# main.net
KiCad netlist of a schematic drawn in Altium Designer
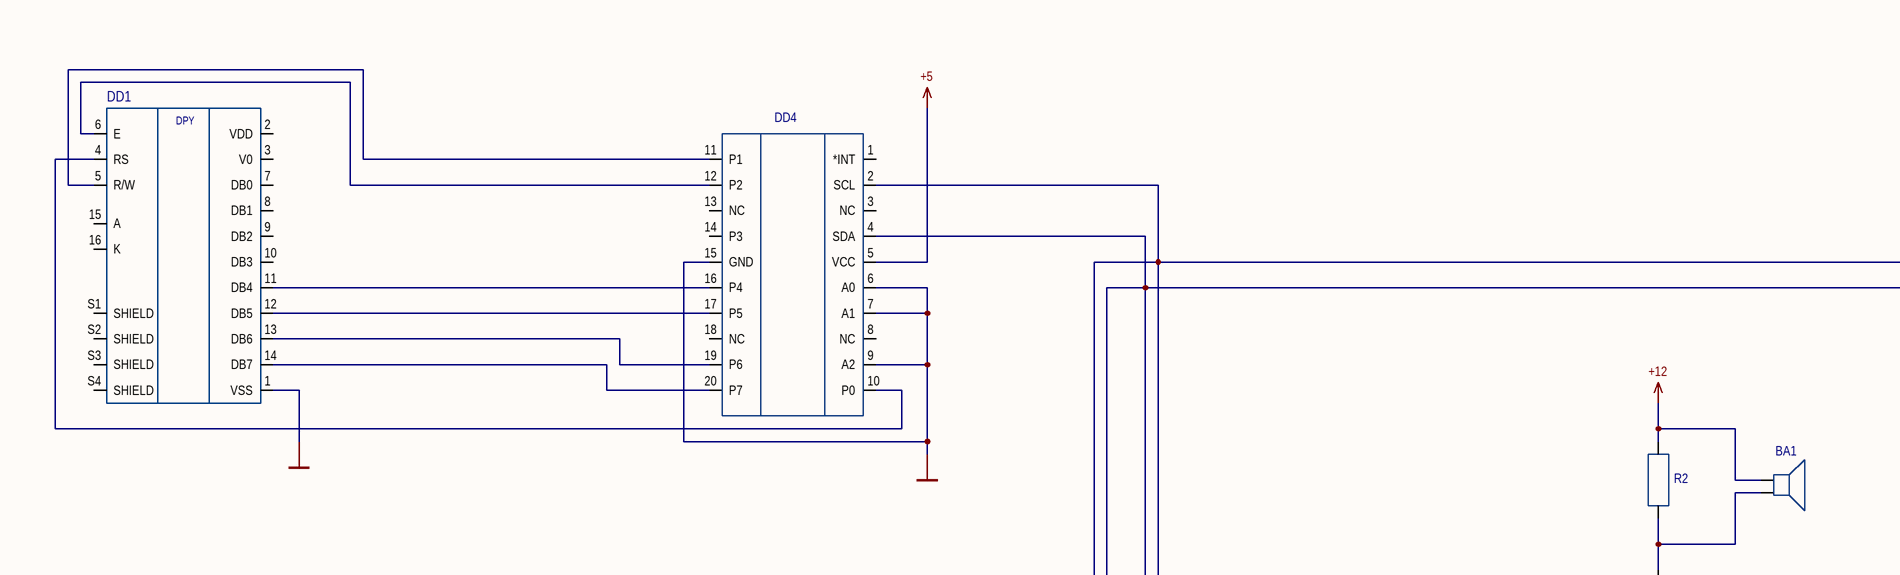
[diagram p0: main.SchDoc, top left]
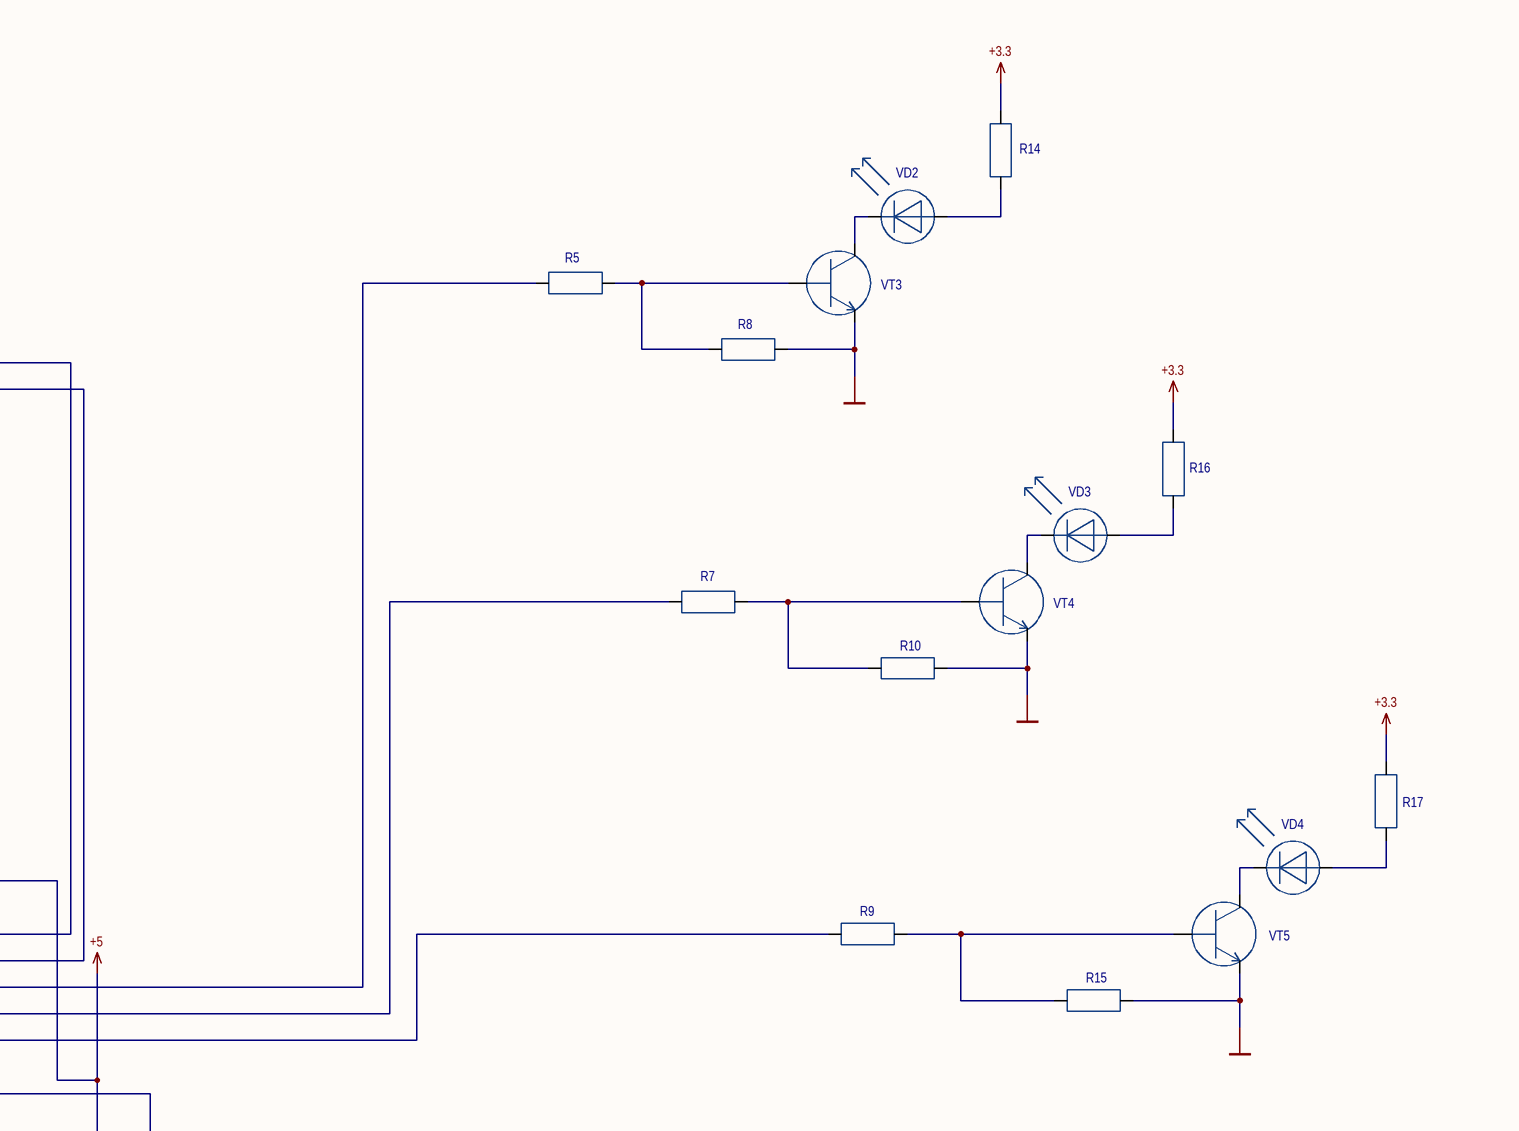
[diagram p1: main.SchDoc, top right]
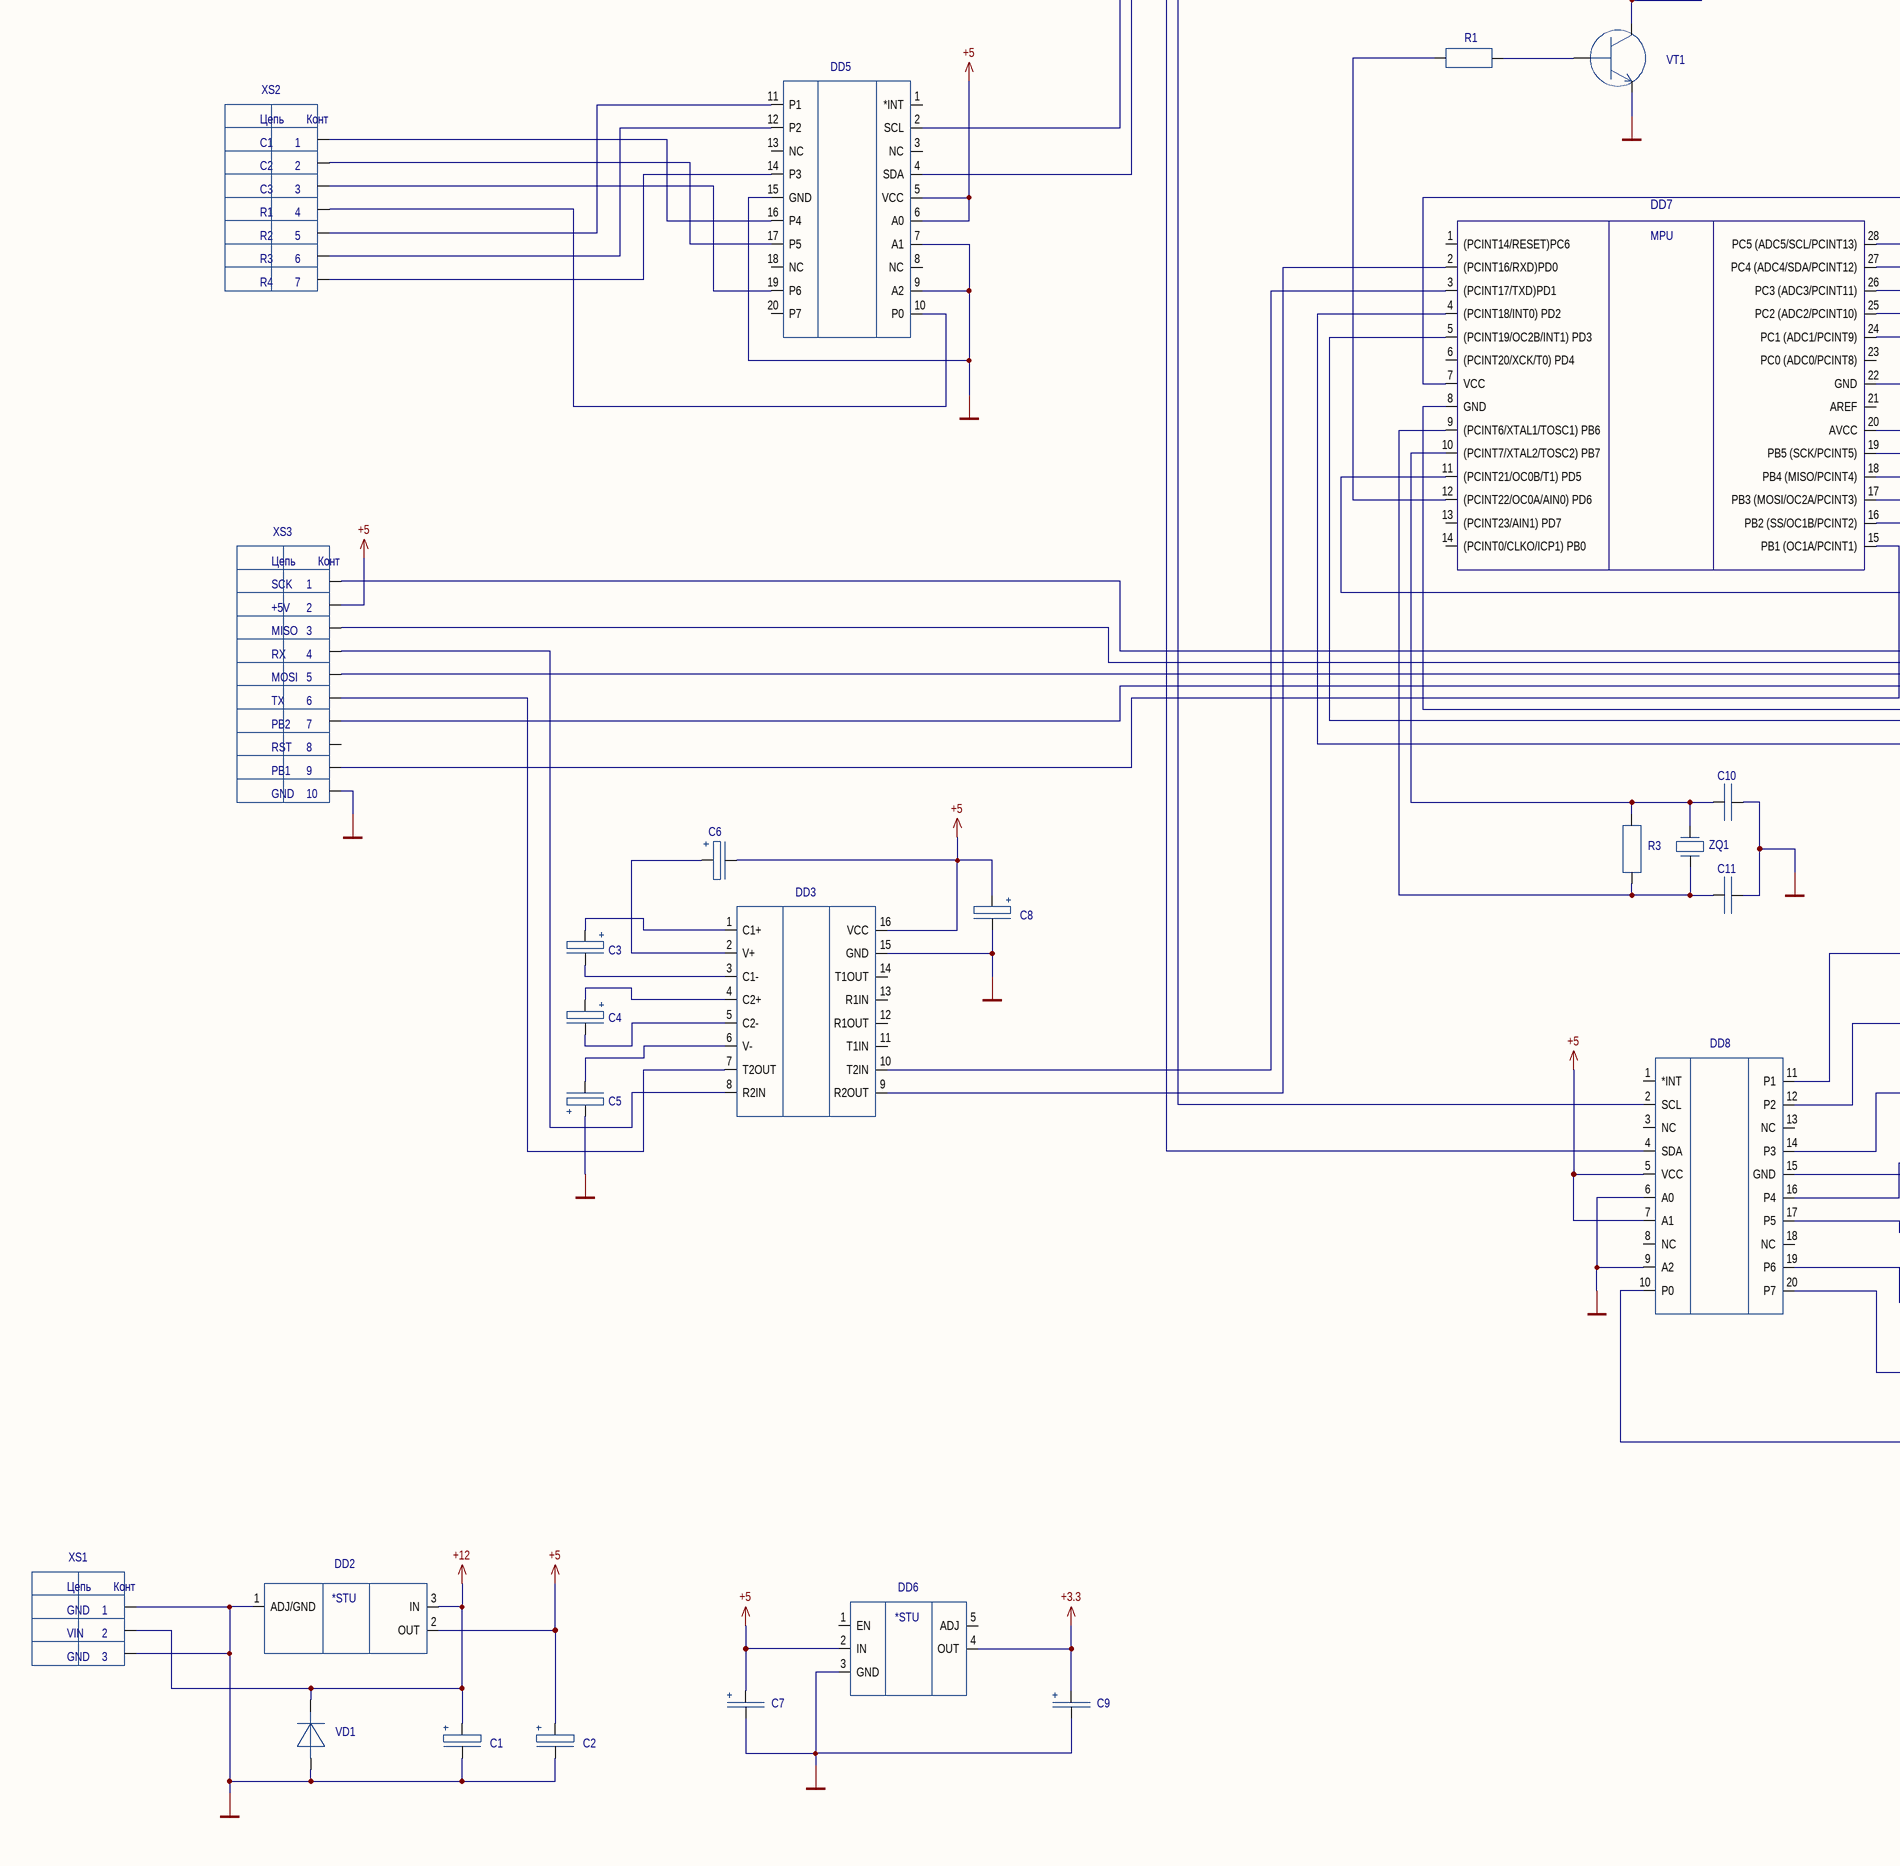
[diagram p2: main.SchDoc, bottom left]
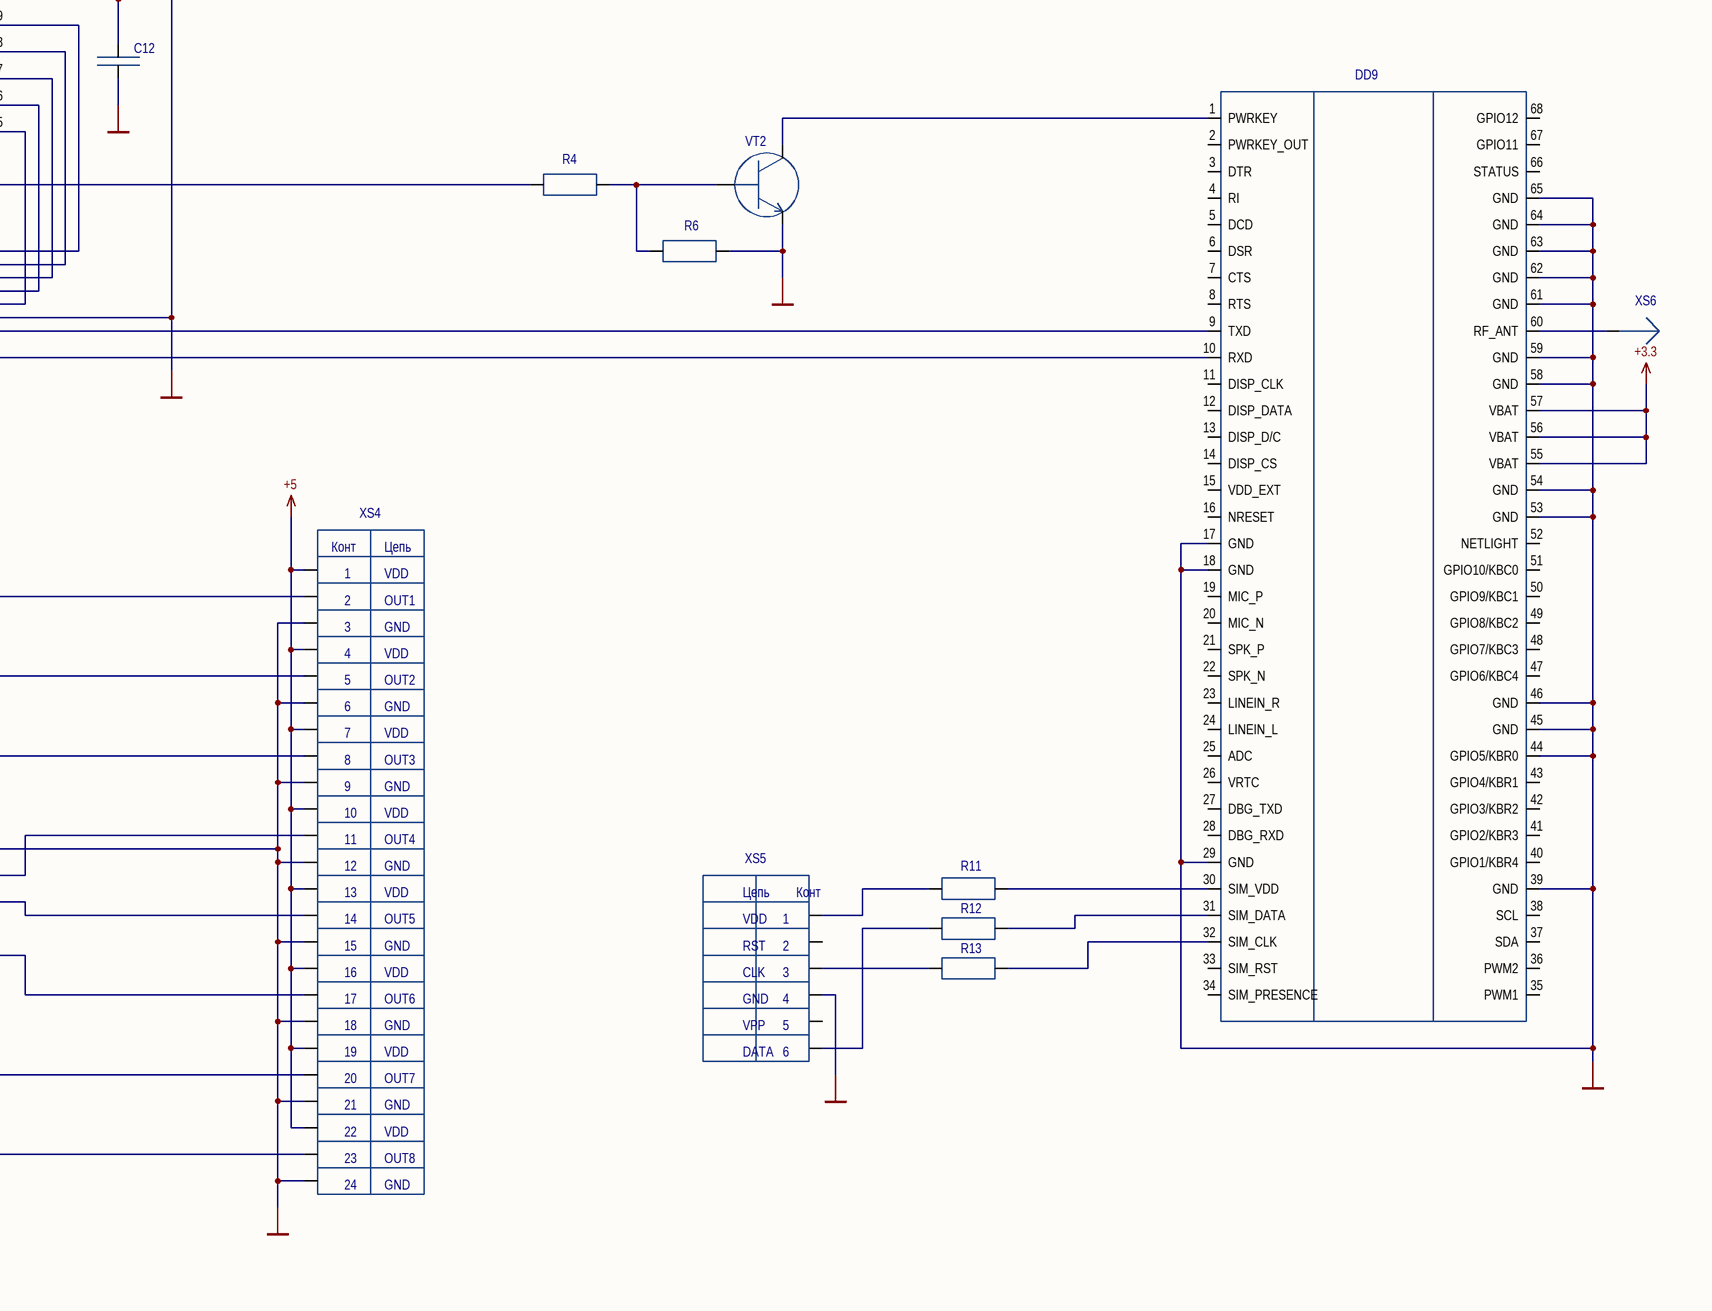
[diagram p3: main.SchDoc, bottom right]

(export (version "E")
  (design (tool "Eeschema 10.0.6"))
  (components
    (comp (ref "BA1")
      (value "speaker_CVS-1508")
      (footprint "diploma:SPeaKeR_CVS-1508")
      (libsource (lib "diploma") (part "speaker_CVS-1508"))
    )
    (comp (ref "C1")
      (value "pol_10mkF")
      (footprint "diploma:PCAP_6_3x11THRU-ELECT_NCA")
      (libsource (lib "diploma") (part "cap_pol_10mkF"))
    )
    (comp (ref "C2")
      (value "pol_10mkF")
      (footprint "diploma:PCAP_6_3x11THRU-ELECT_NCA")
      (libsource (lib "diploma") (part "cap_pol_10mkF"))
    )
    (comp (ref "C3")
      (value "pol_1mkF")
      (footprint "PCAP_5x11-THRU-ELECT_NCA")
      (libsource (lib "diploma") (part "cap_pol_1mkF"))
    )
    (comp (ref "C4")
      (value "pol_1mkF")
      (footprint "PCAP_5x11-THRU-ELECT_NCA")
      (libsource (lib "diploma") (part "cap_pol_1mkF"))
    )
    (comp (ref "C5")
      (value "pol_1mkF")
      (footprint "PCAP_5x11-THRU-ELECT_NCA")
      (libsource (lib "diploma") (part "cap_pol_1mkF"))
    )
    (comp (ref "C6")
      (value "pol_1mkF")
      (footprint "PCAP_5x11-THRU-ELECT_NCA")
      (libsource (lib "diploma") (part "cap_pol_1mkF"))
    )
    (comp (ref "C7")
      (value "pol_100mkF")
      (footprint "diploma:CAP_0805_GRM")
      (libsource (lib "diploma") (part "cap_pol_100mkF"))
    )
    (comp (ref "C8")
      (value "pol_1mkF")
      (footprint "PCAP_5x11-THRU-ELECT_NCA")
      (libsource (lib "diploma") (part "cap_pol_1mkF"))
    )
    (comp (ref "C9")
      (value "pol_100mkF")
      (footprint "diploma:CAP_0805_GRM")
      (libsource (lib "diploma") (part "cap_pol_100mkF"))
    )
    (comp (ref "C10")
      (value "33pF")
      (footprint "diploma:CAP_0805_GRM")
      (libsource (lib "diploma") (part "cap_33pF"))
    )
    (comp (ref "C11")
      (value "33pF")
      (footprint "diploma:CAP_0805_GRM")
      (libsource (lib "diploma") (part "cap_33pF"))
    )
    (comp (ref "C12")
      (value "33pF")
      (footprint "diploma:CAP_0805_GRM")
      (libsource (lib "diploma") (part "cap_33pF"))
    )
    (comp (ref "DD1")
      (value "LCD-20X4B")
      (footprint "LCD_LCD-20X4B")
      (description "Display Development Tools 20X4 CHARACTER BLUE LCD W/BACKLIGHT")
      (fields (field (name "MF") "Gravitech"))
      (libsource (lib "LCD-20X4B") (part "LCD-20X4B"))
    )
    (comp (ref "DD2")
      (value "NCP1117ST50T3G")
      (footprint "SOT223-3_ONS")
      (description "No Description Available")
      (fields (field (name "COPYRIGHT") "Copyright (C) 2016 Accelerated Designs. All rights reserved"))
      (libsource (lib "diploma") (part "stu_NCP1117ST50T3G"))
    )
    (comp (ref "DD3")
      (value "MAX232CSE+")
      (footprint "diploma:max232_dip16")
      (description "No Description Available")
      (fields (field (name "COPYRIGHT") "Copyright (C) 2018 Accelerated Designs. All rights reserved"))
      (libsource (lib "diploma") (part "micro_MAX232"))
    )
    (comp (ref "DD4")
      (value "PCF8574DGVR")
      (footprint "SOT38-4_NXP")
      (description "Remote 8-Bit I/O Expander for I2C-Bus")
      (fields
        (field (name "MANUFACTURER") "Texas Instruments")
        (field (name "GENERIC_PART_NUMBER") "PCF8574")
        (field (name "COPYRIGHT") "Copyright (C) 2018 Accelerated Designs. All rights reserved")
      )
      (libsource (lib "PCF8574DGVR") (part "PCF8574DGVR"))
    )
    (comp (ref "DD5")
      (value "PCF8574DGVR")
      (footprint "SOT38-4_NXP")
      (description "Remote 8-Bit I/O Expander for I2C-Bus")
      (fields
        (field (name "MANUFACTURER") "Texas Instruments")
        (field (name "GENERIC_PART_NUMBER") "PCF8574")
        (field (name "COPYRIGHT") "Copyright (C) 2018 Accelerated Designs. All rights reserved")
      )
      (libsource (lib "PCF8574DGVR") (part "PCF8574DGVR"))
    )
    (comp (ref "DD6")
      (value "stu_MIC29302WT")
      (footprint "diploma:TO-263-5_MCH")
      (libsource (lib "diploma") (part "stu_MIC29302WT"))
    )
    (comp (ref "DD7")
      (value "ATMEGA328P-PU")
      (footprint "28P3_ATM")
      (description "No Description Available")
      (fields (field (name "COPYRIGHT") "Copyright (C) 2018 Accelerated Designs. All rights reserved"))
      (libsource (lib "Atmega328") (part "ATMEGA328P-PU"))
    )
    (comp (ref "DD8")
      (value "PCF8574DGVR")
      (footprint "SOT38-4_NXP")
      (description "Remote 8-Bit I/O Expander for I2C-Bus")
      (fields
        (field (name "MANUFACTURER") "Texas Instruments")
        (field (name "GENERIC_PART_NUMBER") "PCF8574")
        (field (name "COPYRIGHT") "Copyright (C) 2018 Accelerated Designs. All rights reserved")
      )
      (libsource (lib "") (part "PCF8574DGVR_1"))
    )
    (comp (ref "DD9")
      (value "SIM900A")
      (footprint "SIM800A_SMM")
      (libsource (lib "diploma") (part "SIM900A"))
    )
    (comp (ref "R1")
      (value "res_4.7k")
      (footprint "diploma:RC0805N_YAG")
      (libsource (lib "") (part "res_4.7k_2"))
    )
    (comp (ref "R2")
      (value "res_4.7k")
      (footprint "diploma:RC0805N_YAG")
      (libsource (lib "") (part "res_4.7k_1"))
    )
    (comp (ref "R3")
      (value "res_1M")
      (footprint "diploma:RC0805N_YAG")
      (libsource (lib "diploma") (part "res_1M"))
    )
    (comp (ref "R4")
      (value "res_4.7k")
      (footprint "diploma:RC0805N_YAG")
      (libsource (lib "diploma") (part "res_4.7k"))
    )
    (comp (ref "R5")
      (value "res_4.7k")
      (footprint "diploma:RC0805N_YAG")
      (libsource (lib "diploma") (part "res_4.7k"))
    )
    (comp (ref "R6")
      (value "res_4.7k")
      (footprint "diploma:RC0805N_YAG")
      (libsource (lib "diploma") (part "res_4.7k"))
    )
    (comp (ref "R7")
      (value "res_4.7k")
      (footprint "diploma:RC0805N_YAG")
      (libsource (lib "diploma") (part "res_4.7k"))
    )
    (comp (ref "R8")
      (value "res_4.7k")
      (footprint "diploma:RC0805N_YAG")
      (libsource (lib "diploma") (part "res_4.7k"))
    )
    (comp (ref "R9")
      (value "res_4.7k")
      (footprint "diploma:RC0805N_YAG")
      (libsource (lib "diploma") (part "res_4.7k"))
    )
    (comp (ref "R10")
      (value "res_4.7k")
      (footprint "diploma:RC0805N_YAG")
      (libsource (lib "diploma") (part "res_4.7k"))
    )
    (comp (ref "R11")
      (value "res_4.7k")
      (footprint "diploma:RC0805N_YAG")
      (libsource (lib "diploma") (part "res_4.7k"))
    )
    (comp (ref "R12")
      (value "res_4.7k")
      (footprint "diploma:RC0805N_YAG")
      (libsource (lib "diploma") (part "res_4.7k"))
    )
    (comp (ref "R13")
      (value "res_4.7k")
      (footprint "diploma:RC0805N_YAG")
      (libsource (lib "diploma") (part "res_4.7k"))
    )
    (comp (ref "R14")
      (value "res_510")
      (footprint "diploma:RC0805N_YAG")
      (libsource (lib "diploma") (part "res_510"))
    )
    (comp (ref "R15")
      (value "res_4.7k")
      (footprint "diploma:RC0805N_YAG")
      (libsource (lib "diploma") (part "res_4.7k"))
    )
    (comp (ref "R16")
      (value "res_510")
      (footprint "diploma:RC0805N_YAG")
      (libsource (lib "diploma") (part "res_510"))
    )
    (comp (ref "R17")
      (value "res_510")
      (footprint "diploma:RC0805N_YAG")
      (libsource (lib "diploma") (part "res_510"))
    )
    (comp (ref "VD1")
      (value "diode_M7")
      (footprint "diploma:M7_DO-214AC_DTC")
      (libsource (lib "diploma") (part "diode_M7"))
    )
    (comp (ref "VD2")
      (value "diode_red")
      (footprint "diploma:LED_151054RS03000")
      (libsource (lib "diploma") (part "diode_red"))
    )
    (comp (ref "VD3")
      (value "diode_yellow")
      (footprint "diploma:LED_151054RS03000")
      (libsource (lib "diploma") (part "diode_red"))
    )
    (comp (ref "VD4")
      (value "diode_green")
      (footprint "diploma:LED_151054RS03000")
      (libsource (lib "diploma") (part "diode_red"))
    )
    (comp (ref "VT1")
      (value "BC547A")
      (footprint "diploma:TO-92-3_ONS")
      (libsource (lib "diploma") (part "trans_BC547A"))
    )
    (comp (ref "VT2")
      (value "BC547A")
      (footprint "diploma:TO-92-3_ONS")
      (libsource (lib "diploma") (part "trans_BC547A"))
    )
    (comp (ref "VT3")
      (value "BC547A")
      (footprint "diploma:TO-92-3_ONS")
      (libsource (lib "diploma") (part "trans_BC547A"))
    )
    (comp (ref "VT4")
      (value "BC547A")
      (footprint "diploma:TO-92-3_ONS")
      (libsource (lib "diploma") (part "trans_BC547A"))
    )
    (comp (ref "VT5")
      (value "BC547A")
      (footprint "diploma:TO-92-3_ONS")
      (libsource (lib "diploma") (part "trans_BC547A"))
    )
    (comp (ref "XS1")
      (value "DCJ200-10")
      (footprint "diploma:conn_DCJ200-10")
      (libsource (lib "diploma") (part "conn_DCJ200-10_powerIn"))
    )
    (comp (ref "XS2")
      (value "conn_Keypad")
      (footprint "diploma:conn_7pin_TSW-107-05-G-D")
      (libsource (lib "diploma") (part "conn_Keypad"))
    )
    (comp (ref "XS3")
      (value "BH-10")
      (footprint "diploma:conn_10pin_TE_5-102570-3")
      (libsource (lib "diploma") (part "RS-232"))
    )
    (comp (ref "XS4")
      (value "ds1013")
      (footprint "conn_24pin_TSW-108-08-T-T")
      (libsource (lib "diploma") (part "temperature_sensors_connector"))
    )
    (comp (ref "XS5")
      (value "SIM7200-6-0-18-00-X_REVA")
      (footprint "CONN_SIM7200-6-0-18-00-X_REVA")
      (description "No Description Available")
      (fields
        (field (name "MANUFACTURER_PART_NUMBER") "SIM5051-6-0-18-00-A")
        (field (name "COPYRIGHT") "Copyright (C) 2018 Accelerated Designs. All rights reserved")
      )
      (libsource (lib "diploma") (part "conn_SIM7200"))
    )
    (comp (ref "XS6")
      (value "antenn_RECE.20279.001E.01")
      (footprint "diploma:conn_antenn_901-9894-RFX")
      (libsource (lib "diploma") (part "conn_antenn"))
    )
    (comp (ref "ZQ1")
      (value "HC-49S")
      (footprint "diploma:CRYSTAL_HC49S_MTC")
      (libsource (lib "diploma") (part "crystal_8mhz"))
    )
  )
  (nets
    (net (code "1") (name "+3.3") (class "Default")
      (node (ref "C9") (pin "2") (pinfunction "2_2") (pintype "passive"))
      (node (ref "DD6") (pin "4") (pinfunction "OUT_4") (pintype "passive"))
      (node (ref "DD9") (pin "55") (pinfunction "VBAT_55") (pintype "passive"))
      (node (ref "DD9") (pin "56") (pinfunction "VBAT_56") (pintype "passive"))
      (node (ref "DD9") (pin "57") (pinfunction "VBAT_57") (pintype "passive"))
      (node (ref "R14") (pin "2") (pinfunction "2_2") (pintype "passive"))
      (node (ref "R16") (pin "2") (pinfunction "2_2") (pintype "passive"))
      (node (ref "R17") (pin "2") (pinfunction "2_2") (pintype "passive"))
    )
    (net (code "2") (name "+5") (class "Default")
      (node (ref "C12") (pin "2") (pinfunction "2_2") (pintype "passive"))
      (node (ref "C2") (pin "2") (pinfunction "2_2") (pintype "passive"))
      (node (ref "C6") (pin "1") (pinfunction "1_1") (pintype "passive"))
      (node (ref "C7") (pin "2") (pinfunction "2_2") (pintype "passive"))
      (node (ref "C8") (pin "2") (pinfunction "2_2") (pintype "passive"))
      (node (ref "DD2") (pin "2") (pinfunction "OUT_2") (pintype "passive"))
      (node (ref "DD3") (pin "16") (pinfunction "VCC_16") (pintype "passive"))
      (node (ref "DD4") (pin "5") (pinfunction "VCC_5") (pintype "passive"))
      (node (ref "DD5") (pin "5") (pinfunction "VCC_5") (pintype "passive"))
      (node (ref "DD5") (pin "6") (pinfunction "A0_6") (pintype "passive"))
      (node (ref "DD6") (pin "2") (pinfunction "IN_2") (pintype "passive"))
      (node (ref "DD7") (pin "20") (pinfunction "AVCC_20") (pintype "passive"))
      (node (ref "DD7") (pin "7") (pinfunction "VCC_7") (pintype "passive"))
      (node (ref "DD8") (pin "5") (pinfunction "VCC_5") (pintype "passive"))
      (node (ref "DD8") (pin "7") (pinfunction "A1_7") (pintype "passive"))
      (node (ref "XS3") (pin "2") (pinfunction "VDD_2") (pintype "passive"))
      (node (ref "XS4") (pin "1") (pinfunction "VSS_1") (pintype "passive"))
      (node (ref "XS4") (pin "10") (pinfunction "D3_10") (pintype "passive"))
      (node (ref "XS4") (pin "13") (pinfunction "D6_13") (pintype "passive"))
      (node (ref "XS4") (pin "16") (pinfunction "16_16") (pintype "passive"))
      (node (ref "XS4") (pin "19") (pinfunction "19_19") (pintype "passive"))
      (node (ref "XS4") (pin "22") (pinfunction "22_22") (pintype "passive"))
      (node (ref "XS4") (pin "4") (pinfunction "C/D_4") (pintype "passive"))
      (node (ref "XS4") (pin "7") (pinfunction "D0_7") (pintype "passive"))
    )
    (net (code "3") (name "+12") (class "Default")
      (node (ref "BA1") (pin "1") (pinfunction "1_1") (pintype "passive"))
      (node (ref "C1") (pin "2") (pinfunction "2_2") (pintype "passive"))
      (node (ref "DD2") (pin "3") (pinfunction "IN_3") (pintype "passive"))
      (node (ref "R2") (pin "2") (pinfunction "2_2") (pintype "passive"))
      (node (ref "VD1") (pin "2") (pinfunction "2_2") (pintype "passive"))
      (node (ref "XS1") (pin "2") (pinfunction "GND_2") (pintype "passive"))
    )
    (net (code "4") (name "GND") (class "Default")
      (node (ref "C1") (pin "1") (pinfunction "1_1") (pintype "passive"))
      (node (ref "C10") (pin "2") (pinfunction "2_2") (pintype "passive"))
      (node (ref "C11") (pin "2") (pinfunction "2_2") (pintype "passive"))
      (node (ref "C12") (pin "1") (pinfunction "1_1") (pintype "passive"))
      (node (ref "C2") (pin "1") (pinfunction "1_1") (pintype "passive"))
      (node (ref "C5") (pin "2") (pinfunction "2_2") (pintype "passive"))
      (node (ref "C7") (pin "1") (pinfunction "1_1") (pintype "passive"))
      (node (ref "C8") (pin "1") (pinfunction "1_1") (pintype "passive"))
      (node (ref "C9") (pin "1") (pinfunction "1_1") (pintype "passive"))
      (node (ref "DD1") (pin "1") (pinfunction "VSS_1") (pintype "passive"))
      (node (ref "DD2") (pin "1") (pinfunction "ADJ/GND_1") (pintype "passive"))
      (node (ref "DD3") (pin "15") (pinfunction "GND_15") (pintype "passive"))
      (node (ref "DD4") (pin "15") (pinfunction "GND_15") (pintype "passive"))
      (node (ref "DD4") (pin "6") (pinfunction "A0_6") (pintype "passive"))
      (node (ref "DD4") (pin "7") (pinfunction "A1_7") (pintype "passive"))
      (node (ref "DD4") (pin "9") (pinfunction "A2_9") (pintype "passive"))
      (node (ref "DD5") (pin "15") (pinfunction "GND_15") (pintype "passive"))
      (node (ref "DD5") (pin "7") (pinfunction "A1_7") (pintype "passive"))
      (node (ref "DD5") (pin "9") (pinfunction "A2_9") (pintype "passive"))
      (node (ref "DD6") (pin "3") (pinfunction "GND_3") (pintype "passive"))
      (node (ref "DD7") (pin "22") (pinfunction "GND_22") (pintype "passive"))
      (node (ref "DD7") (pin "8") (pinfunction "GND_8") (pintype "passive"))
      (node (ref "DD8") (pin "15") (pinfunction "GND_15") (pintype "passive"))
      (node (ref "DD8") (pin "6") (pinfunction "A0_6") (pintype "passive"))
      (node (ref "DD8") (pin "9") (pinfunction "A2_9") (pintype "passive"))
      (node (ref "DD9") (pin "17") (pinfunction "GND_17") (pintype "passive"))
      (node (ref "DD9") (pin "18") (pinfunction "GND_18") (pintype "passive"))
      (node (ref "DD9") (pin "29") (pinfunction "GND_29") (pintype "passive"))
      (node (ref "DD9") (pin "39") (pinfunction "GND_39") (pintype "passive"))
      (node (ref "DD9") (pin "44") (pinfunction "GPIO5/KBR0_44") (pintype "passive"))
      (node (ref "DD9") (pin "45") (pinfunction "GND_45") (pintype "passive"))
      (node (ref "DD9") (pin "46") (pinfunction "GND_46") (pintype "passive"))
      (node (ref "DD9") (pin "53") (pinfunction "GND_53") (pintype "passive"))
      (node (ref "DD9") (pin "54") (pinfunction "GND_54") (pintype "passive"))
      (node (ref "DD9") (pin "58") (pinfunction "GND_58") (pintype "passive"))
      (node (ref "DD9") (pin "59") (pinfunction "GND_59") (pintype "passive"))
      (node (ref "DD9") (pin "61") (pinfunction "GND_61") (pintype "passive"))
      (node (ref "DD9") (pin "62") (pinfunction "GND_62") (pintype "passive"))
      (node (ref "DD9") (pin "63") (pinfunction "GND_63") (pintype "passive"))
      (node (ref "DD9") (pin "64") (pinfunction "GND_64") (pintype "passive"))
      (node (ref "DD9") (pin "65") (pinfunction "GND_65") (pintype "passive"))
      (node (ref "R10") (pin "2") (pinfunction "2_2") (pintype "passive"))
      (node (ref "R15") (pin "2") (pinfunction "2_2") (pintype "passive"))
      (node (ref "R6") (pin "2") (pinfunction "2_2") (pintype "passive"))
      (node (ref "R8") (pin "2") (pinfunction "2_2") (pintype "passive"))
      (node (ref "VD1") (pin "1") (pinfunction "1_1") (pintype "passive"))
      (node (ref "VT1") (pin "1") (pinfunction "E_1") (pintype "passive"))
      (node (ref "VT2") (pin "1") (pinfunction "E_1") (pintype "passive"))
      (node (ref "VT3") (pin "1") (pinfunction "E_1") (pintype "passive"))
      (node (ref "VT4") (pin "1") (pinfunction "E_1") (pintype "passive"))
      (node (ref "VT5") (pin "1") (pinfunction "E_1") (pintype "passive"))
      (node (ref "XS1") (pin "1") (pinfunction "+5V_1") (pintype "passive"))
      (node (ref "XS1") (pin "3") (pinfunction "SCL_3") (pintype "passive"))
      (node (ref "XS3") (pin "10") (pinfunction "D3_10") (pintype "passive"))
      (node (ref "XS4") (pin "12") (pinfunction "D5_12") (pintype "passive"))
      (node (ref "XS4") (pin "15") (pinfunction "15_15") (pintype "passive"))
      (node (ref "XS4") (pin "18") (pinfunction "18_18") (pintype "passive"))
      (node (ref "XS4") (pin "21") (pinfunction "21_21") (pintype "passive"))
      (node (ref "XS4") (pin "24") (pinfunction "24_24") (pintype "passive"))
      (node (ref "XS4") (pin "3") (pinfunction "VO_3") (pintype "passive"))
      (node (ref "XS4") (pin "6") (pinfunction "*WR_6") (pintype "passive"))
      (node (ref "XS4") (pin "9") (pinfunction "D2_9") (pintype "passive"))
      (node (ref "XS5") (pin "4") (pinfunction "GND_4") (pintype "passive"))
    )
    (net (code "5") (name "Net-(DD1-DB4)") (class "Default")
      (node (ref "DD1") (pin "11") (pinfunction "DB4_11") (pintype "passive"))
      (node (ref "DD4") (pin "16") (pinfunction "P4_16") (pintype "passive"))
    )
    (net (code "6") (name "Net-(DD1-DB5)") (class "Default")
      (node (ref "DD1") (pin "12") (pinfunction "DB5_12") (pintype "passive"))
      (node (ref "DD4") (pin "17") (pinfunction "P5_17") (pintype "passive"))
    )
    (net (code "7") (name "Net-(DD1-DB6)") (class "Default")
      (node (ref "DD1") (pin "13") (pinfunction "DB6_13") (pintype "passive"))
      (node (ref "DD4") (pin "19") (pinfunction "P6_19") (pintype "passive"))
    )
    (net (code "8") (name "Net-(DD1-DB7)") (class "Default")
      (node (ref "DD1") (pin "14") (pinfunction "DB7_14") (pintype "passive"))
      (node (ref "DD4") (pin "20") (pinfunction "P7_20") (pintype "passive"))
    )
    (net (code "9") (name "Net-(DD1-E)") (class "Default")
      (node (ref "DD1") (pin "6") (pinfunction "E_6") (pintype "passive"))
      (node (ref "DD4") (pin "12") (pinfunction "P2_12") (pintype "passive"))
    )
    (net (code "10") (name "Net-(DD1-RS)") (class "Default")
      (node (ref "DD1") (pin "4") (pinfunction "RS_4") (pintype "passive"))
      (node (ref "DD4") (pin "10") (pinfunction "P0_10") (pintype "passive"))
    )
    (net (code "11") (name "Net-(DD1-R{slash}W)") (class "Default")
      (node (ref "DD1") (pin "5") (pinfunction "R/W_5") (pintype "passive"))
      (node (ref "DD4") (pin "11") (pinfunction "P1_11") (pintype "passive"))
    )
    (net (code "12") (name "Net-(DD3-C1+)") (class "Default")
      (node (ref "C3") (pin "2") (pinfunction "2_2") (pintype "passive"))
      (node (ref "DD3") (pin "1") (pinfunction "C1+_1") (pintype "passive"))
    )
    (net (code "13") (name "Net-(DD3-C1-)") (class "Default")
      (node (ref "C3") (pin "1") (pinfunction "1_1") (pintype "passive"))
      (node (ref "DD3") (pin "3") (pinfunction "C1-_3") (pintype "passive"))
    )
    (net (code "14") (name "Net-(DD3-C2+)") (class "Default")
      (node (ref "C4") (pin "2") (pinfunction "2_2") (pintype "passive"))
      (node (ref "DD3") (pin "4") (pinfunction "C2+_4") (pintype "passive"))
    )
    (net (code "15") (name "Net-(DD3-C2-)") (class "Default")
      (node (ref "C4") (pin "1") (pinfunction "1_1") (pintype "passive"))
      (node (ref "DD3") (pin "5") (pinfunction "C2-_5") (pintype "passive"))
    )
    (net (code "16") (name "Net-(DD3-R2IN)") (class "Default")
      (node (ref "DD3") (pin "8") (pinfunction "R2IN_8") (pintype "passive"))
      (node (ref "XS3") (pin "4") (pinfunction "C/D_4") (pintype "passive"))
    )
    (net (code "17") (name "Net-(DD3-R2OUT)") (class "Default")
      (node (ref "DD3") (pin "9") (pinfunction "R2OUT_9") (pintype "passive"))
      (node (ref "DD7") (pin "2") (pinfunction "(PCINT16/RXD)PD0_2") (pintype "passive"))
    )
    (net (code "18") (name "Net-(DD3-T2IN)") (class "Default")
      (node (ref "DD3") (pin "10") (pinfunction "T2IN_10") (pintype "passive"))
      (node (ref "DD7") (pin "3") (pinfunction "(PCINT17/TXD)PD1_3") (pintype "passive"))
    )
    (net (code "19") (name "Net-(DD3-T2OUT)") (class "Default")
      (node (ref "DD3") (pin "7") (pinfunction "T2OUT_7") (pintype "passive"))
      (node (ref "XS3") (pin "6") (pinfunction "*WR_6") (pintype "passive"))
    )
    (net (code "20") (name "Net-(DD3-V+)") (class "Default")
      (node (ref "C6") (pin "2") (pinfunction "2_2") (pintype "passive"))
      (node (ref "DD3") (pin "2") (pinfunction "V+_2") (pintype "passive"))
    )
    (net (code "21") (name "Net-(DD3-V-)") (class "Default")
      (node (ref "C5") (pin "1") (pinfunction "1_1") (pintype "passive"))
      (node (ref "DD3") (pin "6") (pinfunction "V-_6") (pintype "passive"))
    )
    (net (code "22") (name "Net-(DD4-SCL)") (class "Default")
      (node (ref "DD4") (pin "2") (pinfunction "SCL_2") (pintype "passive"))
      (node (ref "DD5") (pin "2") (pinfunction "SCL_2") (pintype "passive"))
      (node (ref "DD7") (pin "28") (pinfunction "PC5_(ADC5/SCL/PCINT13)_28") (pintype "passive"))
      (node (ref "DD8") (pin "2") (pinfunction "SCL_2") (pintype "passive"))
    )
    (net (code "23") (name "Net-(DD4-SDA)") (class "Default")
      (node (ref "DD4") (pin "4") (pinfunction "SDA_4") (pintype "passive"))
      (node (ref "DD5") (pin "4") (pinfunction "SDA_4") (pintype "passive"))
      (node (ref "DD7") (pin "27") (pinfunction "PC4_(ADC4/SDA/PCINT12)_27") (pintype "passive"))
      (node (ref "DD8") (pin "4") (pinfunction "SDA_4") (pintype "passive"))
    )
    (net (code "24") (name "Net-(DD5-P0)") (class "Default")
      (node (ref "DD5") (pin "10") (pinfunction "P0_10") (pintype "passive"))
      (node (ref "XS2") (pin "4") (pinfunction "C/D_4") (pintype "passive"))
    )
    (net (code "25") (name "Net-(DD5-P1)") (class "Default")
      (node (ref "DD5") (pin "11") (pinfunction "P1_11") (pintype "passive"))
      (node (ref "XS2") (pin "5") (pinfunction "*RD_5") (pintype "passive"))
    )
    (net (code "26") (name "Net-(DD5-P2)") (class "Default")
      (node (ref "DD5") (pin "12") (pinfunction "P2_12") (pintype "passive"))
      (node (ref "XS2") (pin "6") (pinfunction "*WR_6") (pintype "passive"))
    )
    (net (code "27") (name "Net-(DD5-P3)") (class "Default")
      (node (ref "DD5") (pin "14") (pinfunction "P3_14") (pintype "passive"))
      (node (ref "XS2") (pin "7") (pinfunction "D0_7") (pintype "passive"))
    )
    (net (code "28") (name "Net-(DD5-P4)") (class "Default")
      (node (ref "DD5") (pin "16") (pinfunction "P4_16") (pintype "passive"))
      (node (ref "XS2") (pin "1") (pinfunction "VSS_1") (pintype "passive"))
    )
    (net (code "29") (name "Net-(DD5-P5)") (class "Default")
      (node (ref "DD5") (pin "17") (pinfunction "P5_17") (pintype "passive"))
      (node (ref "XS2") (pin "2") (pinfunction "VDD_2") (pintype "passive"))
    )
    (net (code "30") (name "Net-(DD5-P6)") (class "Default")
      (node (ref "DD5") (pin "19") (pinfunction "P6_19") (pintype "passive"))
      (node (ref "XS2") (pin "3") (pinfunction "VO_3") (pintype "passive"))
    )
    (net (code "31") (name "Net-(DD7-(PCINT6{slash}XTAL1{slash}TOSC1)_PB6)") (class "Default")
      (node (ref "C11") (pin "1") (pinfunction "1_1") (pintype "passive"))
      (node (ref "DD7") (pin "9") (pinfunction "(PCINT6/XTAL1/TOSC1)_PB6_9") (pintype "passive"))
      (node (ref "R3") (pin "1") (pinfunction "1_1") (pintype "passive"))
      (node (ref "ZQ1") (pin "1") (pinfunction "1_1") (pintype "passive"))
    )
    (net (code "32") (name "Net-(DD7-(PCINT7{slash}XTAL2{slash}TOSC2)_PB7)") (class "Default")
      (node (ref "C10") (pin "1") (pinfunction "1_1") (pintype "passive"))
      (node (ref "DD7") (pin "10") (pinfunction "(PCINT7/XTAL2/TOSC2)_PB7_10") (pintype "passive"))
      (node (ref "R3") (pin "2") (pinfunction "2_2") (pintype "passive"))
      (node (ref "ZQ1") (pin "2") (pinfunction "2_2") (pintype "passive"))
    )
    (net (code "33") (name "Net-(DD7-(PCINT18{slash}INT0)_PD2)") (class "Default")
      (node (ref "DD7") (pin "4") (pinfunction "(PCINT18/INT0)_PD2_4") (pintype "passive"))
      (node (ref "DD9") (pin "10") (pinfunction "RXD_10") (pintype "passive"))
    )
    (net (code "34") (name "Net-(DD7-(PCINT19{slash}OC2B{slash}INT1)_PD3)") (class "Default")
      (node (ref "DD7") (pin "5") (pinfunction "(PCINT19/OC2B/INT1)_PD3_5") (pintype "passive"))
      (node (ref "DD9") (pin "9") (pinfunction "TXD_9") (pintype "passive"))
    )
    (net (code "35") (name "Net-(DD7-(PCINT21{slash}OC0B{slash}T1)_PD5)") (class "Default")
      (node (ref "DD7") (pin "11") (pinfunction "(PCINT21/OC0B/T1)_PD5_11") (pintype "passive"))
      (node (ref "R4") (pin "1") (pinfunction "1_1") (pintype "passive"))
    )
    (net (code "36") (name "Net-(DD7-(PCINT22{slash}OC0A{slash}AIN0)_PD6)") (class "Default")
      (node (ref "DD7") (pin "12") (pinfunction "(PCINT22/OC0A/AIN0)_PD6_12") (pintype "passive"))
      (node (ref "R1") (pin "2") (pinfunction "2_2") (pintype "passive"))
    )
    (net (code "37") (name "Net-(DD7-PB1_(OC1A{slash}PCINT1))") (class "Default")
      (node (ref "DD7") (pin "15") (pinfunction "PB1_(OC1A/PCINT1)_15") (pintype "passive"))
      (node (ref "XS3") (pin "9") (pinfunction "D2_9") (pintype "passive"))
    )
    (net (code "38") (name "Net-(DD7-PB2_(SS{slash}OC1B{slash}PCINT2))") (class "Default")
      (node (ref "DD7") (pin "16") (pinfunction "PB2_(SS/OC1B/PCINT2)_16") (pintype "passive"))
      (node (ref "XS3") (pin "7") (pinfunction "D0_7") (pintype "passive"))
    )
    (net (code "39") (name "Net-(DD7-PB3_(MOSI{slash}OC2A{slash}PCINT3))") (class "Default")
      (node (ref "DD7") (pin "17") (pinfunction "PB3_(MOSI/OC2A/PCINT3)_17") (pintype "passive"))
      (node (ref "XS3") (pin "5") (pinfunction "*RD_5") (pintype "passive"))
    )
    (net (code "40") (name "Net-(DD7-PB4_(MISO{slash}PCINT4))") (class "Default")
      (node (ref "DD7") (pin "18") (pinfunction "PB4_(MISO/PCINT4)_18") (pintype "passive"))
      (node (ref "XS3") (pin "3") (pinfunction "VO_3") (pintype "passive"))
    )
    (net (code "41") (name "Net-(DD7-PB5_(SCK{slash}PCINT5))") (class "Default")
      (node (ref "DD7") (pin "19") (pinfunction "PB5_(SCK/PCINT5)_19") (pintype "passive"))
      (node (ref "XS3") (pin "1") (pinfunction "VSS_1") (pintype "passive"))
    )
    (net (code "42") (name "Net-(DD7-PC1_(ADC1{slash}PCINT9))") (class "Default")
      (node (ref "DD7") (pin "24") (pinfunction "PC1_(ADC1/PCINT9)_24") (pintype "passive"))
      (node (ref "R9") (pin "1") (pinfunction "1_1") (pintype "passive"))
    )
    (net (code "43") (name "Net-(DD7-PC2_(ADC2{slash}PCINT10))") (class "Default")
      (node (ref "DD7") (pin "25") (pinfunction "PC2_(ADC2/PCINT10)_25") (pintype "passive"))
      (node (ref "R7") (pin "1") (pinfunction "1_1") (pintype "passive"))
    )
    (net (code "44") (name "Net-(DD7-PC3_(ADC3{slash}PCINT11))") (class "Default")
      (node (ref "DD7") (pin "26") (pinfunction "PC3_(ADC3/PCINT11)_26") (pintype "passive"))
      (node (ref "R5") (pin "1") (pinfunction "1_1") (pintype "passive"))
    )
    (net (code "45") (name "Net-(DD8-P0)") (class "Default")
      (node (ref "DD8") (pin "10") (pinfunction "P0_10") (pintype "passive"))
      (node (ref "XS4") (pin "23") (pinfunction "23_23") (pintype "passive"))
    )
    (net (code "46") (name "Net-(DD8-P1)") (class "Default")
      (node (ref "DD8") (pin "11") (pinfunction "P1_11") (pintype "passive"))
      (node (ref "XS4") (pin "2") (pinfunction "VDD_2") (pintype "passive"))
    )
    (net (code "47") (name "Net-(DD8-P2)") (class "Default")
      (node (ref "DD8") (pin "12") (pinfunction "P2_12") (pintype "passive"))
      (node (ref "XS4") (pin "5") (pinfunction "*RD_5") (pintype "passive"))
    )
    (net (code "48") (name "Net-(DD8-P3)") (class "Default")
      (node (ref "DD8") (pin "14") (pinfunction "P3_14") (pintype "passive"))
      (node (ref "XS4") (pin "8") (pinfunction "D1_8") (pintype "passive"))
    )
    (net (code "49") (name "Net-(DD8-P4)") (class "Default")
      (node (ref "DD8") (pin "16") (pinfunction "P4_16") (pintype "passive"))
      (node (ref "XS4") (pin "11") (pinfunction "D4_11") (pintype "passive"))
    )
    (net (code "50") (name "Net-(DD8-P5)") (class "Default")
      (node (ref "DD8") (pin "17") (pinfunction "P5_17") (pintype "passive"))
      (node (ref "XS4") (pin "14") (pinfunction "D7_14") (pintype "passive"))
    )
    (net (code "51") (name "Net-(DD8-P6)") (class "Default")
      (node (ref "DD8") (pin "19") (pinfunction "P6_19") (pintype "passive"))
      (node (ref "XS4") (pin "17") (pinfunction "17_17") (pintype "passive"))
    )
    (net (code "52") (name "Net-(DD8-P7)") (class "Default")
      (node (ref "DD8") (pin "20") (pinfunction "P7_20") (pintype "passive"))
      (node (ref "XS4") (pin "20") (pinfunction "20_20") (pintype "passive"))
    )
    (net (code "53") (name "Net-(DD9-PWRKEY)") (class "Default")
      (node (ref "DD9") (pin "1") (pinfunction "PWRKEY_1") (pintype "passive"))
      (node (ref "VT2") (pin "3") (pinfunction "C_3") (pintype "passive"))
    )
    (net (code "54") (name "Net-(DD9-RF_ANT)") (class "Default")
      (node (ref "DD9") (pin "60") (pinfunction "RF_ANT_60") (pintype "passive"))
      (node (ref "XS6") (pin "1") (pinfunction "1_1") (pintype "passive"))
    )
    (net (code "55") (name "Net-(DD9-SIM_CLK)") (class "Default")
      (node (ref "DD9") (pin "32") (pinfunction "SIM_CLK_32") (pintype "passive"))
      (node (ref "R13") (pin "2") (pinfunction "2_2") (pintype "passive"))
    )
    (net (code "56") (name "Net-(DD9-SIM_DATA)") (class "Default")
      (node (ref "DD9") (pin "31") (pinfunction "SIM_DATA_31") (pintype "passive"))
      (node (ref "R12") (pin "2") (pinfunction "2_2") (pintype "passive"))
    )
    (net (code "57") (name "Net-(DD9-SIM_VDD)") (class "Default")
      (node (ref "DD9") (pin "30") (pinfunction "SIM_VDD_30") (pintype "passive"))
      (node (ref "R11") (pin "2") (pinfunction "2_2") (pintype "passive"))
    )
    (net (code "58") (name "Net-(R14-Pad1)") (class "Default")
      (node (ref "R14") (pin "1") (pinfunction "1_1") (pintype "passive"))
      (node (ref "VD2") (pin "1") (pinfunction "1_1") (pintype "passive"))
    )
    (net (code "59") (name "Net-(R16-Pad1)") (class "Default")
      (node (ref "R16") (pin "1") (pinfunction "1_1") (pintype "passive"))
      (node (ref "VD3") (pin "1") (pinfunction "1_1") (pintype "passive"))
    )
    (net (code "60") (name "Net-(R17-Pad1)") (class "Default")
      (node (ref "R17") (pin "1") (pinfunction "1_1") (pintype "passive"))
      (node (ref "VD4") (pin "1") (pinfunction "1_1") (pintype "passive"))
    )
    (net (code "61") (name "Net-(VT1-B)") (class "Default")
      (node (ref "R1") (pin "1") (pinfunction "1_1") (pintype "passive"))
      (node (ref "VT1") (pin "2") (pinfunction "B_2") (pintype "passive"))
    )
    (net (code "62") (name "Net-(VT1-C)") (class "Default")
      (node (ref "BA1") (pin "2") (pinfunction "2_2") (pintype "passive"))
      (node (ref "R2") (pin "1") (pinfunction "1_1") (pintype "passive"))
      (node (ref "VT1") (pin "3") (pinfunction "C_3") (pintype "passive"))
    )
    (net (code "63") (name "Net-(VT2-B)") (class "Default")
      (node (ref "R4") (pin "2") (pinfunction "2_2") (pintype "passive"))
      (node (ref "R6") (pin "1") (pinfunction "1_1") (pintype "passive"))
      (node (ref "VT2") (pin "2") (pinfunction "B_2") (pintype "passive"))
    )
    (net (code "64") (name "Net-(VT3-B)") (class "Default")
      (node (ref "R5") (pin "2") (pinfunction "2_2") (pintype "passive"))
      (node (ref "R8") (pin "1") (pinfunction "1_1") (pintype "passive"))
      (node (ref "VT3") (pin "2") (pinfunction "B_2") (pintype "passive"))
    )
    (net (code "65") (name "Net-(VT3-C)") (class "Default")
      (node (ref "VD2") (pin "2") (pinfunction "2_2") (pintype "passive"))
      (node (ref "VT3") (pin "3") (pinfunction "C_3") (pintype "passive"))
    )
    (net (code "66") (name "Net-(VT4-B)") (class "Default")
      (node (ref "R10") (pin "1") (pinfunction "1_1") (pintype "passive"))
      (node (ref "R7") (pin "2") (pinfunction "2_2") (pintype "passive"))
      (node (ref "VT4") (pin "2") (pinfunction "B_2") (pintype "passive"))
    )
    (net (code "67") (name "Net-(VT4-C)") (class "Default")
      (node (ref "VD3") (pin "2") (pinfunction "2_2") (pintype "passive"))
      (node (ref "VT4") (pin "3") (pinfunction "C_3") (pintype "passive"))
    )
    (net (code "68") (name "Net-(VT5-B)") (class "Default")
      (node (ref "R15") (pin "1") (pinfunction "1_1") (pintype "passive"))
      (node (ref "R9") (pin "2") (pinfunction "2_2") (pintype "passive"))
      (node (ref "VT5") (pin "2") (pinfunction "B_2") (pintype "passive"))
    )
    (net (code "69") (name "Net-(VT5-C)") (class "Default")
      (node (ref "VD4") (pin "2") (pinfunction "2_2") (pintype "passive"))
      (node (ref "VT5") (pin "3") (pinfunction "C_3") (pintype "passive"))
    )
    (net (code "70") (name "Net-(XS5-CLK)") (class "Default")
      (node (ref "R13") (pin "1") (pinfunction "1_1") (pintype "passive"))
      (node (ref "XS5") (pin "3") (pinfunction "CLK_3") (pintype "passive"))
    )
    (net (code "71") (name "Net-(XS5-I{slash}O)") (class "Default")
      (node (ref "R12") (pin "1") (pinfunction "1_1") (pintype "passive"))
      (node (ref "XS5") (pin "6") (pinfunction "I/O_6") (pintype "passive"))
    )
    (net (code "72") (name "Net-(XS5-VCC)") (class "Default")
      (node (ref "R11") (pin "1") (pinfunction "1_1") (pintype "passive"))
      (node (ref "XS5") (pin "1") (pinfunction "VCC_1") (pintype "power_in"))
    )
    (net (code "73") (name "unconnected-(DD1-A-Pad15)") (class "Default")
      (node (ref "DD1") (pin "15") (pinfunction "A_15") (pintype "passive"))
    )
    (net (code "74") (name "unconnected-(DD1-DB0-Pad7)") (class "Default")
      (node (ref "DD1") (pin "7") (pinfunction "DB0_7") (pintype "passive"))
    )
    (net (code "75") (name "unconnected-(DD1-DB1-Pad8)") (class "Default")
      (node (ref "DD1") (pin "8") (pinfunction "DB1_8") (pintype "passive"))
    )
    (net (code "76") (name "unconnected-(DD1-DB2-Pad9)") (class "Default")
      (node (ref "DD1") (pin "9") (pinfunction "DB2_9") (pintype "passive"))
    )
    (net (code "77") (name "unconnected-(DD1-DB3-Pad10)") (class "Default")
      (node (ref "DD1") (pin "10") (pinfunction "DB3_10") (pintype "passive"))
    )
    (net (code "78") (name "unconnected-(DD1-K-Pad16)") (class "Default")
      (node (ref "DD1") (pin "16") (pinfunction "K_16") (pintype "passive"))
    )
    (net (code "79") (name "unconnected-(DD1-SHIELD-PadS1)") (class "Default")
      (node (ref "DD1") (pin "S1") (pinfunction "SHIELD_S1") (pintype "passive"))
    )
    (net (code "80") (name "unconnected-(DD1-SHIELD-PadS2)") (class "Default")
      (node (ref "DD1") (pin "S2") (pinfunction "SHIELD_S2") (pintype "passive"))
    )
    (net (code "81") (name "unconnected-(DD1-SHIELD-PadS3)") (class "Default")
      (node (ref "DD1") (pin "S3") (pinfunction "SHIELD_S3") (pintype "passive"))
    )
    (net (code "82") (name "unconnected-(DD1-SHIELD-PadS4)") (class "Default")
      (node (ref "DD1") (pin "S4") (pinfunction "SHIELD_S4") (pintype "passive"))
    )
    (net (code "83") (name "unconnected-(DD1-V0-Pad3)") (class "Default")
      (node (ref "DD1") (pin "3") (pinfunction "V0_3") (pintype "passive"))
    )
    (net (code "84") (name "unconnected-(DD1-VDD-Pad2)") (class "Default")
      (node (ref "DD1") (pin "2") (pinfunction "VDD_2") (pintype "passive"))
    )
    (net (code "85") (name "unconnected-(DD3-R1IN-Pad13)") (class "Default")
      (node (ref "DD3") (pin "13") (pinfunction "R1IN_13") (pintype "passive"))
    )
    (net (code "86") (name "unconnected-(DD3-R1OUT-Pad12)") (class "Default")
      (node (ref "DD3") (pin "12") (pinfunction "R1OUT_12") (pintype "passive"))
    )
    (net (code "87") (name "unconnected-(DD3-T1IN-Pad11)") (class "Default")
      (node (ref "DD3") (pin "11") (pinfunction "T1IN_11") (pintype "passive"))
    )
    (net (code "88") (name "unconnected-(DD3-T1OUT-Pad14)") (class "Default")
      (node (ref "DD3") (pin "14") (pinfunction "T1OUT_14") (pintype "passive"))
    )
    (net (code "89") (name "unconnected-(DD4-*INT-Pad1)") (class "Default")
      (node (ref "DD4") (pin "1") (pinfunction "*INT_1") (pintype "passive"))
    )
    (net (code "90") (name "unconnected-(DD4-NC-Pad3)") (class "Default")
      (node (ref "DD4") (pin "3") (pinfunction "NC_3") (pintype "passive"))
    )
    (net (code "91") (name "unconnected-(DD4-NC-Pad8)") (class "Default")
      (node (ref "DD4") (pin "8") (pinfunction "NC_8") (pintype "passive"))
    )
    (net (code "92") (name "unconnected-(DD4-NC-Pad13)") (class "Default")
      (node (ref "DD4") (pin "13") (pinfunction "NC_13") (pintype "passive"))
    )
    (net (code "93") (name "unconnected-(DD4-NC-Pad18)") (class "Default")
      (node (ref "DD4") (pin "18") (pinfunction "NC_18") (pintype "passive"))
    )
    (net (code "94") (name "unconnected-(DD4-P3-Pad14)") (class "Default")
      (node (ref "DD4") (pin "14") (pinfunction "P3_14") (pintype "passive"))
    )
    (net (code "95") (name "unconnected-(DD5-*INT-Pad1)") (class "Default")
      (node (ref "DD5") (pin "1") (pinfunction "*INT_1") (pintype "passive"))
    )
    (net (code "96") (name "unconnected-(DD5-NC-Pad3)") (class "Default")
      (node (ref "DD5") (pin "3") (pinfunction "NC_3") (pintype "passive"))
    )
    (net (code "97") (name "unconnected-(DD5-NC-Pad8)") (class "Default")
      (node (ref "DD5") (pin "8") (pinfunction "NC_8") (pintype "passive"))
    )
    (net (code "98") (name "unconnected-(DD5-NC-Pad13)") (class "Default")
      (node (ref "DD5") (pin "13") (pinfunction "NC_13") (pintype "passive"))
    )
    (net (code "99") (name "unconnected-(DD5-NC-Pad18)") (class "Default")
      (node (ref "DD5") (pin "18") (pinfunction "NC_18") (pintype "passive"))
    )
    (net (code "100") (name "unconnected-(DD5-P7-Pad20)") (class "Default")
      (node (ref "DD5") (pin "20") (pinfunction "P7_20") (pintype "passive"))
    )
    (net (code "101") (name "unconnected-(DD6-ADJ-Pad5)") (class "Default")
      (node (ref "DD6") (pin "5") (pinfunction "ADJ_5") (pintype "passive"))
    )
    (net (code "102") (name "unconnected-(DD6-EN-Pad1)") (class "Default")
      (node (ref "DD6") (pin "1") (pinfunction "EN_1") (pintype "passive"))
    )
    (net (code "103") (name "unconnected-(DD7-(PCINT0{slash}CLKO{slash}ICP1)_PB0-Pad14)") (class "Default")
      (node (ref "DD7") (pin "14") (pinfunction "(PCINT0/CLKO/ICP1)_PB0_14") (pintype "passive"))
    )
    (net (code "104") (name "unconnected-(DD7-(PCINT14{slash}RESET)PC6-Pad1)") (class "Default")
      (node (ref "DD7") (pin "1") (pinfunction "(PCINT14/RESET)PC6_1") (pintype "passive"))
    )
    (net (code "105") (name "unconnected-(DD7-(PCINT20{slash}XCK{slash}T0)_PD4-Pad6)") (class "Default")
      (node (ref "DD7") (pin "6") (pinfunction "(PCINT20/XCK/T0)_PD4_6") (pintype "passive"))
    )
    (net (code "106") (name "unconnected-(DD7-(PCINT23{slash}AIN1)_PD7-Pad13)") (class "Default")
      (node (ref "DD7") (pin "13") (pinfunction "(PCINT23/AIN1)_PD7_13") (pintype "passive"))
    )
    (net (code "107") (name "unconnected-(DD7-AREF-Pad21)") (class "Default")
      (node (ref "DD7") (pin "21") (pinfunction "AREF_21") (pintype "passive"))
    )
    (net (code "108") (name "unconnected-(DD7-PC0_(ADC0{slash}PCINT8)-Pad23)") (class "Default")
      (node (ref "DD7") (pin "23") (pinfunction "PC0_(ADC0/PCINT8)_23") (pintype "passive"))
    )
    (net (code "109") (name "unconnected-(DD8-*INT-Pad1)") (class "Default")
      (node (ref "DD8") (pin "1") (pinfunction "*INT_1") (pintype "passive"))
    )
    (net (code "110") (name "unconnected-(DD8-NC-Pad3)") (class "Default")
      (node (ref "DD8") (pin "3") (pinfunction "NC_3") (pintype "passive"))
    )
    (net (code "111") (name "unconnected-(DD8-NC-Pad8)") (class "Default")
      (node (ref "DD8") (pin "8") (pinfunction "NC_8") (pintype "passive"))
    )
    (net (code "112") (name "unconnected-(DD8-NC-Pad13)") (class "Default")
      (node (ref "DD8") (pin "13") (pinfunction "NC_13") (pintype "passive"))
    )
    (net (code "113") (name "unconnected-(DD8-NC-Pad18)") (class "Default")
      (node (ref "DD8") (pin "18") (pinfunction "NC_18") (pintype "passive"))
    )
    (net (code "114") (name "unconnected-(DD9-ADC-Pad25)") (class "Default")
      (node (ref "DD9") (pin "25") (pinfunction "ADC_25") (pintype "passive"))
    )
    (net (code "115") (name "unconnected-(DD9-CTS-Pad7)") (class "Default")
      (node (ref "DD9") (pin "7") (pinfunction "CTS_7") (pintype "passive"))
    )
    (net (code "116") (name "unconnected-(DD9-DBG_RXD-Pad28)") (class "Default")
      (node (ref "DD9") (pin "28") (pinfunction "DBG_RXD_28") (pintype "passive"))
    )
    (net (code "117") (name "unconnected-(DD9-DBG_TXD-Pad27)") (class "Default")
      (node (ref "DD9") (pin "27") (pinfunction "DBG_TXD_27") (pintype "passive"))
    )
    (net (code "118") (name "unconnected-(DD9-DCD-Pad5)") (class "Default")
      (node (ref "DD9") (pin "5") (pinfunction "DCD_5") (pintype "passive"))
    )
    (net (code "119") (name "unconnected-(DD9-DISP_CLK-Pad11)") (class "Default")
      (node (ref "DD9") (pin "11") (pinfunction "DISP_CLK_11") (pintype "passive"))
    )
    (net (code "120") (name "unconnected-(DD9-DISP_CS-Pad14)") (class "Default")
      (node (ref "DD9") (pin "14") (pinfunction "DISP_CS_14") (pintype "passive"))
    )
    (net (code "121") (name "unconnected-(DD9-DISP_DATA-Pad12)") (class "Default")
      (node (ref "DD9") (pin "12") (pinfunction "DISP_DATA_12") (pintype "passive"))
    )
    (net (code "122") (name "unconnected-(DD9-DISP_D{slash}C-Pad13)") (class "Default")
      (node (ref "DD9") (pin "13") (pinfunction "DISP_D/C_13") (pintype "passive"))
    )
    (net (code "123") (name "unconnected-(DD9-DSR-Pad6)") (class "Default")
      (node (ref "DD9") (pin "6") (pinfunction "DSR_6") (pintype "passive"))
    )
    (net (code "124") (name "unconnected-(DD9-DTR-Pad3)") (class "Default")
      (node (ref "DD9") (pin "3") (pinfunction "DTR_3") (pintype "passive"))
    )
    (net (code "125") (name "unconnected-(DD9-GPIO1{slash}KBR4-Pad40)") (class "Default")
      (node (ref "DD9") (pin "40") (pinfunction "GPIO1/KBR4_40") (pintype "passive"))
    )
    (net (code "126") (name "unconnected-(DD9-GPIO2{slash}KBR3-Pad41)") (class "Default")
      (node (ref "DD9") (pin "41") (pinfunction "GPIO2/KBR3_41") (pintype "passive"))
    )
    (net (code "127") (name "unconnected-(DD9-GPIO3{slash}KBR2-Pad42)") (class "Default")
      (node (ref "DD9") (pin "42") (pinfunction "GPIO3/KBR2_42") (pintype "passive"))
    )
    (net (code "128") (name "unconnected-(DD9-GPIO4{slash}KBR1-Pad43)") (class "Default")
      (node (ref "DD9") (pin "43") (pinfunction "GPIO4/KBR1_43") (pintype "passive"))
    )
    (net (code "129") (name "unconnected-(DD9-GPIO6{slash}KBC4-Pad47)") (class "Default")
      (node (ref "DD9") (pin "47") (pinfunction "GPIO6/KBC4_47") (pintype "passive"))
    )
    (net (code "130") (name "unconnected-(DD9-GPIO7{slash}KBC3-Pad48)") (class "Default")
      (node (ref "DD9") (pin "48") (pinfunction "GPIO7/KBC3_48") (pintype "passive"))
    )
    (net (code "131") (name "unconnected-(DD9-GPIO8{slash}KBC2-Pad49)") (class "Default")
      (node (ref "DD9") (pin "49") (pinfunction "GPIO8/KBC2_49") (pintype "passive"))
    )
    (net (code "132") (name "unconnected-(DD9-GPIO9{slash}KBC1-Pad50)") (class "Default")
      (node (ref "DD9") (pin "50") (pinfunction "GPIO9/KBC1_50") (pintype "passive"))
    )
    (net (code "133") (name "unconnected-(DD9-GPIO10{slash}KBC0-Pad51)") (class "Default")
      (node (ref "DD9") (pin "51") (pinfunction "GPIO10/KBC0_51") (pintype "passive"))
    )
    (net (code "134") (name "unconnected-(DD9-GPIO11-Pad67)") (class "Default")
      (node (ref "DD9") (pin "67") (pinfunction "GPIO11_67") (pintype "passive"))
    )
    (net (code "135") (name "unconnected-(DD9-GPIO12-Pad68)") (class "Default")
      (node (ref "DD9") (pin "68") (pinfunction "GPIO12_68") (pintype "passive"))
    )
    (net (code "136") (name "unconnected-(DD9-LINEIN_L-Pad24)") (class "Default")
      (node (ref "DD9") (pin "24") (pinfunction "LINEIN_L_24") (pintype "passive"))
    )
    (net (code "137") (name "unconnected-(DD9-LINEIN_R-Pad23)") (class "Default")
      (node (ref "DD9") (pin "23") (pinfunction "LINEIN_R_23") (pintype "passive"))
    )
    (net (code "138") (name "unconnected-(DD9-MIC_N-Pad20)") (class "Default")
      (node (ref "DD9") (pin "20") (pinfunction "MIC_N_20") (pintype "passive"))
    )
    (net (code "139") (name "unconnected-(DD9-MIC_P-Pad19)") (class "Default")
      (node (ref "DD9") (pin "19") (pinfunction "MIC_P_19") (pintype "passive"))
    )
    (net (code "140") (name "unconnected-(DD9-NETLIGHT-Pad52)") (class "Default")
      (node (ref "DD9") (pin "52") (pinfunction "NETLIGHT_52") (pintype "passive"))
    )
    (net (code "141") (name "unconnected-(DD9-NRESET-Pad16)") (class "Default")
      (node (ref "DD9") (pin "16") (pinfunction "NRESET_16") (pintype "passive"))
    )
    (net (code "142") (name "unconnected-(DD9-PWM1-Pad35)") (class "Default")
      (node (ref "DD9") (pin "35") (pinfunction "PWM1_35") (pintype "passive"))
    )
    (net (code "143") (name "unconnected-(DD9-PWM2-Pad36)") (class "Default")
      (node (ref "DD9") (pin "36") (pinfunction "PWM2_36") (pintype "passive"))
    )
    (net (code "144") (name "unconnected-(DD9-PWRKEY_OUT-Pad2)") (class "Default")
      (node (ref "DD9") (pin "2") (pinfunction "PWRKEY_OUT_2") (pintype "passive"))
    )
    (net (code "145") (name "unconnected-(DD9-RI-Pad4)") (class "Default")
      (node (ref "DD9") (pin "4") (pinfunction "RI_4") (pintype "passive"))
    )
    (net (code "146") (name "unconnected-(DD9-RTS-Pad8)") (class "Default")
      (node (ref "DD9") (pin "8") (pinfunction "RTS_8") (pintype "passive"))
    )
    (net (code "147") (name "unconnected-(DD9-SCL-Pad38)") (class "Default")
      (node (ref "DD9") (pin "38") (pinfunction "SCL_38") (pintype "passive"))
    )
    (net (code "148") (name "unconnected-(DD9-SDA-Pad37)") (class "Default")
      (node (ref "DD9") (pin "37") (pinfunction "SDA_37") (pintype "passive"))
    )
    (net (code "149") (name "unconnected-(DD9-SIM_PRESENCE-Pad34)") (class "Default")
      (node (ref "DD9") (pin "34") (pinfunction "SIM_PRESENCE_34") (pintype "passive"))
    )
    (net (code "150") (name "unconnected-(DD9-SIM_RST-Pad33)") (class "Default")
      (node (ref "DD9") (pin "33") (pinfunction "SIM_RST_33") (pintype "passive"))
    )
    (net (code "151") (name "unconnected-(DD9-SPK_N-Pad22)") (class "Default")
      (node (ref "DD9") (pin "22") (pinfunction "SPK_N_22") (pintype "passive"))
    )
    (net (code "152") (name "unconnected-(DD9-SPK_P-Pad21)") (class "Default")
      (node (ref "DD9") (pin "21") (pinfunction "SPK_P_21") (pintype "passive"))
    )
    (net (code "153") (name "unconnected-(DD9-STATUS-Pad66)") (class "Default")
      (node (ref "DD9") (pin "66") (pinfunction "STATUS_66") (pintype "passive"))
    )
    (net (code "154") (name "unconnected-(DD9-VDD_EXT-Pad15)") (class "Default")
      (node (ref "DD9") (pin "15") (pinfunction "VDD_EXT_15") (pintype "passive"))
    )
    (net (code "155") (name "unconnected-(DD9-VRTC-Pad26)") (class "Default")
      (node (ref "DD9") (pin "26") (pinfunction "VRTC_26") (pintype "passive"))
    )
    (net (code "156") (name "unconnected-(XS3-D1-Pad8)") (class "Default")
      (node (ref "XS3") (pin "8") (pinfunction "D1_8") (pintype "passive"))
    )
    (net (code "157") (name "unconnected-(XS5-RST-Pad2)") (class "Default")
      (node (ref "XS5") (pin "2") (pinfunction "RST_2") (pintype "passive"))
    )
    (net (code "158") (name "unconnected-(XS5-VPP-Pad5)") (class "Default")
      (node (ref "XS5") (pin "5") (pinfunction "VPP_5") (pintype "power_in"))
    )
  )
)
